# Connect_4_robot_main.net
KiCad netlist of a schematic drawn in EasyEDA
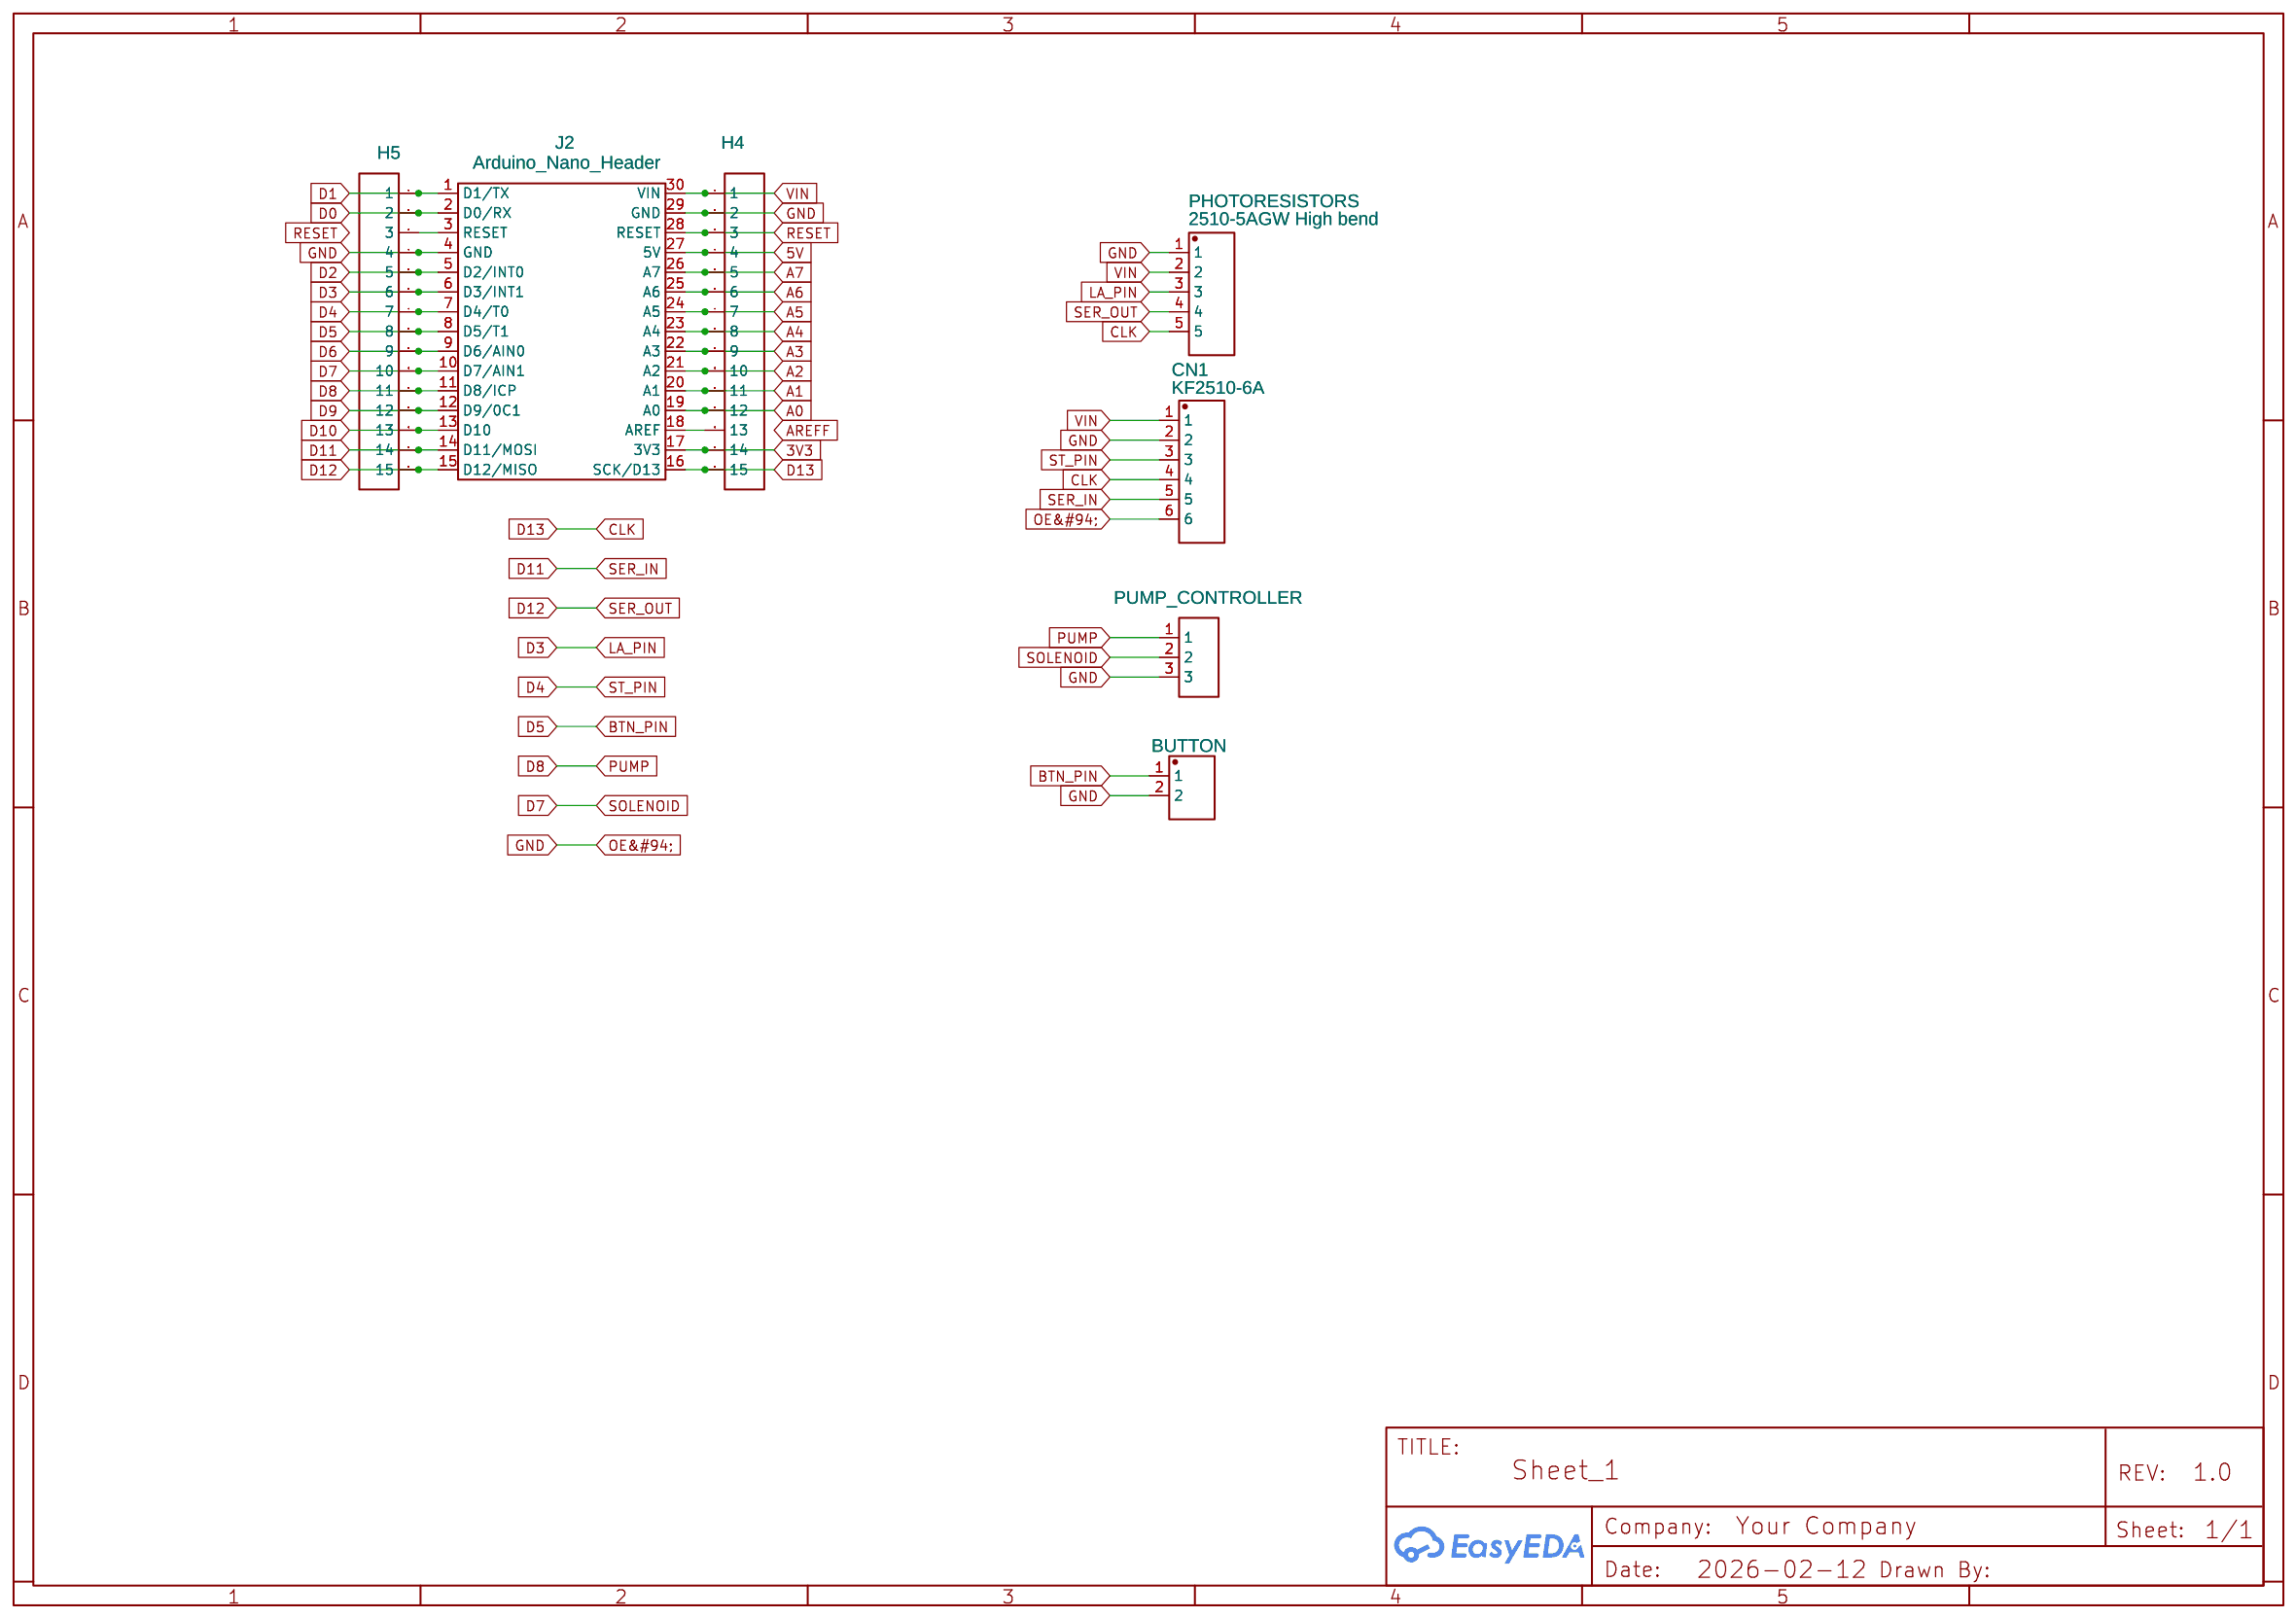
[diagram p0: schematic sheet]

(export (version "E")
  (design (tool "Eeschema 10.0.6"))
  (components
    (comp (ref "CN1")
      (value "KF2510-6A")
      (fields (field (name "Manufacturer Part") "KF2510-6A针座"))
      (libsource (lib "") (part "KF2510-6A"))
    )
    (comp (ref "D3")
      (value "BUTTON")
      (fields (field (name "Manufacturer Part") "KF2510-2A") (field (name "Manufacturer") "BOOMELE"))
      (libsource (lib "") (part "KF2510-2A"))
    )
    (comp (ref "H4") (value "HDR-F-2.54_1x15") (libsource (lib "") (part "HDR-F-2.54_1x15_1")))
    (comp (ref "H5") (value "HDR-F-2.54_1x15") (libsource (lib "") (part "HDR-F-2.54_1x15")))
    (comp (ref "J2") (value "Arduino_Nano_Header") (libsource (lib "") (part "Arduino_Nano_Header")))
    (comp (ref "PHOTORESISTORS")
      (value "2510-5AGW High bend")
      (fields (field (name "Manufacturer Part") "2510-5A高弯") (field (name "Manufacturer") "BOOMELE(博穆精密)"))
      (libsource (lib "") (part "2510-5AGW High bend"))
    )
    (comp (ref "PUMP_CONTROLLER") (value "FK2510") (libsource (lib "") (part "kf2510_3A")))
  )
  (nets
    (net (code "1") (name "3V3") (class "Default")
      (node (ref "H4") (pin "14") (pinfunction "14_14") (pintype "unspecified"))
      (node (ref "J2") (pin "17") (pinfunction "3V3_17") (pintype "unspecified"))
    )
    (net (code "2") (name "5V") (class "Default")
      (node (ref "H4") (pin "4") (pinfunction "4_4") (pintype "unspecified"))
      (node (ref "J2") (pin "27") (pinfunction "5V_27") (pintype "unspecified"))
    )
    (net (code "3") (name "A0") (class "Default")
      (node (ref "H4") (pin "12") (pinfunction "12_12") (pintype "unspecified"))
      (node (ref "J2") (pin "19") (pinfunction "A0_19") (pintype "unspecified"))
    )
    (net (code "4") (name "A1") (class "Default")
      (node (ref "H4") (pin "11") (pinfunction "11_11") (pintype "unspecified"))
      (node (ref "J2") (pin "20") (pinfunction "A1_20") (pintype "unspecified"))
    )
    (net (code "5") (name "A2") (class "Default")
      (node (ref "H4") (pin "10") (pinfunction "10_10") (pintype "unspecified"))
      (node (ref "J2") (pin "21") (pinfunction "A2_21") (pintype "unspecified"))
    )
    (net (code "6") (name "A3") (class "Default")
      (node (ref "H4") (pin "9") (pinfunction "9_9") (pintype "unspecified"))
      (node (ref "J2") (pin "22") (pinfunction "A3_22") (pintype "unspecified"))
    )
    (net (code "7") (name "A4") (class "Default")
      (node (ref "H4") (pin "8") (pinfunction "8_8") (pintype "unspecified"))
      (node (ref "J2") (pin "23") (pinfunction "A4_23") (pintype "unspecified"))
    )
    (net (code "8") (name "A5") (class "Default")
      (node (ref "H4") (pin "7") (pinfunction "7_7") (pintype "unspecified"))
      (node (ref "J2") (pin "24") (pinfunction "A5_24") (pintype "unspecified"))
    )
    (net (code "9") (name "A6") (class "Default")
      (node (ref "H4") (pin "6") (pinfunction "6_6") (pintype "unspecified"))
      (node (ref "J2") (pin "25") (pinfunction "A6_25") (pintype "unspecified"))
    )
    (net (code "10") (name "A7") (class "Default")
      (node (ref "H4") (pin "5") (pinfunction "5_5") (pintype "unspecified"))
      (node (ref "J2") (pin "26") (pinfunction "A7_26") (pintype "unspecified"))
    )
    (net (code "12") (name "BTN_PIN") (class "Default")
      (node (ref "D3") (pin "1") (pinfunction "1_1") (pintype "unspecified"))
      (node (ref "H5") (pin "8") (pinfunction "8_8") (pintype "unspecified"))
      (node (ref "J2") (pin "8") (pinfunction "D5/T1_8") (pintype "unspecified"))
    )
    (net (code "13") (name "CLK") (class "Default")
      (node (ref "CN1") (pin "4") (pinfunction "4_4") (pintype "unspecified"))
      (node (ref "H4") (pin "15") (pinfunction "15_15") (pintype "unspecified"))
      (node (ref "J2") (pin "16") (pinfunction "SCK/D13_16") (pintype "unspecified"))
      (node (ref "PHOTORESISTORS") (pin "5") (pinfunction "5_5") (pintype "unspecified"))
    )
    (net (code "14") (name "D0") (class "Default")
      (node (ref "H5") (pin "2") (pinfunction "2_2") (pintype "unspecified"))
      (node (ref "J2") (pin "2") (pinfunction "D0/RX_2") (pintype "unspecified"))
    )
    (net (code "15") (name "D1") (class "Default")
      (node (ref "H5") (pin "1") (pinfunction "1_1") (pintype "unspecified"))
      (node (ref "J2") (pin "1") (pinfunction "D1/TX_1") (pintype "unspecified"))
    )
    (net (code "16") (name "D2") (class "Default")
      (node (ref "H5") (pin "5") (pinfunction "5_5") (pintype "unspecified"))
      (node (ref "J2") (pin "5") (pinfunction "D2/INT0_5") (pintype "unspecified"))
    )
    (net (code "17") (name "D3") (class "Default")
      (node (ref "H5") (pin "6") (pinfunction "6_6") (pintype "unspecified"))
      (node (ref "J2") (pin "6") (pinfunction "D3/INT1_6") (pintype "unspecified"))
      (node (ref "PHOTORESISTORS") (pin "3") (pinfunction "3_3") (pintype "unspecified"))
    )
    (net (code "18") (name "D4") (class "Default")
      (node (ref "CN1") (pin "3") (pinfunction "3_3") (pintype "unspecified"))
      (node (ref "H5") (pin "7") (pinfunction "7_7") (pintype "unspecified"))
      (node (ref "J2") (pin "7") (pinfunction "D4/T0_7") (pintype "unspecified"))
    )
    (net (code "19") (name "D6") (class "Default")
      (node (ref "H5") (pin "9") (pinfunction "9_9") (pintype "unspecified"))
      (node (ref "J2") (pin "9") (pinfunction "D6/AIN0_9") (pintype "unspecified"))
    )
    (net (code "20") (name "D7") (class "Default")
      (node (ref "H5") (pin "10") (pinfunction "10_10") (pintype "unspecified"))
      (node (ref "J2") (pin "10") (pinfunction "D7/AIN1_10") (pintype "unspecified"))
      (node (ref "PUMP_CONTROLLER") (pin "2") (pinfunction "2_2") (pintype "unspecified"))
    )
    (net (code "21") (name "D8") (class "Default")
      (node (ref "H5") (pin "11") (pinfunction "11_11") (pintype "unspecified"))
      (node (ref "J2") (pin "11") (pinfunction "D8/ICP_11") (pintype "unspecified"))
      (node (ref "PUMP_CONTROLLER") (pin "1") (pinfunction "1_1") (pintype "unspecified"))
    )
    (net (code "22") (name "D9") (class "Default")
      (node (ref "H5") (pin "12") (pinfunction "12_12") (pintype "unspecified"))
      (node (ref "J2") (pin "12") (pinfunction "D9/0C1_12") (pintype "unspecified"))
    )
    (net (code "23") (name "D10") (class "Default")
      (node (ref "H5") (pin "13") (pinfunction "13_13") (pintype "unspecified"))
      (node (ref "J2") (pin "13") (pinfunction "D10_13") (pintype "unspecified"))
    )
    (net (code "24") (name "D11") (class "Default")
      (node (ref "CN1") (pin "5") (pinfunction "5_5") (pintype "unspecified"))
      (node (ref "H5") (pin "14") (pinfunction "14_14") (pintype "unspecified"))
      (node (ref "J2") (pin "14") (pinfunction "D11/MOSI_14") (pintype "unspecified"))
    )
    (net (code "25") (name "D12") (class "Default")
      (node (ref "H5") (pin "15") (pinfunction "15_15") (pintype "unspecified"))
      (node (ref "J2") (pin "15") (pinfunction "D12/MISO_15") (pintype "unspecified"))
      (node (ref "PHOTORESISTORS") (pin "4") (pinfunction "4_4") (pintype "unspecified"))
    )
    (net (code "26") (name "GND") (class "Default")
      (node (ref "CN1") (pin "2") (pinfunction "2_2") (pintype "unspecified"))
      (node (ref "CN1") (pin "6") (pinfunction "6_6") (pintype "unspecified"))
      (node (ref "D3") (pin "2") (pinfunction "2_2") (pintype "unspecified"))
      (node (ref "H4") (pin "2") (pinfunction "2_2") (pintype "unspecified"))
      (node (ref "H5") (pin "4") (pinfunction "4_4") (pintype "unspecified"))
      (node (ref "J2") (pin "29") (pinfunction "GND_29") (pintype "unspecified"))
      (node (ref "J2") (pin "4") (pinfunction "GND_4") (pintype "unspecified"))
      (node (ref "PHOTORESISTORS") (pin "1") (pinfunction "1_1") (pintype "unspecified"))
      (node (ref "PUMP_CONTROLLER") (pin "3") (pinfunction "3_3") (pintype "unspecified"))
    )
    (net (code "27") (name "Net-(H5-Pad3)") (class "Default")
      (node (ref "H5") (pin "3") (pinfunction "3_3") (pintype "unspecified"))
      (node (ref "J2") (pin "3") (pinfunction "RESET_3") (pintype "unspecified"))
    )
    (net (code "28") (name "Net-(J2-AREF)") (class "Default")
      (node (ref "H4") (pin "13") (pinfunction "13_13") (pintype "unspecified"))
      (node (ref "J2") (pin "18") (pinfunction "AREF_18") (pintype "unspecified"))
    )
    (net (code "29") (name "RESET") (class "Default")
      (node (ref "H4") (pin "3") (pinfunction "3_3") (pintype "unspecified"))
      (node (ref "J2") (pin "28") (pinfunction "RESET_28") (pintype "unspecified"))
    )
    (net (code "30") (name "VIN") (class "Default")
      (node (ref "CN1") (pin "1") (pinfunction "1_1") (pintype "unspecified"))
      (node (ref "H4") (pin "1") (pinfunction "1_1") (pintype "unspecified"))
      (node (ref "J2") (pin "30") (pinfunction "VIN_30") (pintype "unspecified"))
      (node (ref "PHOTORESISTORS") (pin "2") (pinfunction "2_2") (pintype "unspecified"))
    )
  )
)
